# alarm_module.net
KiCad netlist of a schematic drawn in Altium Designer
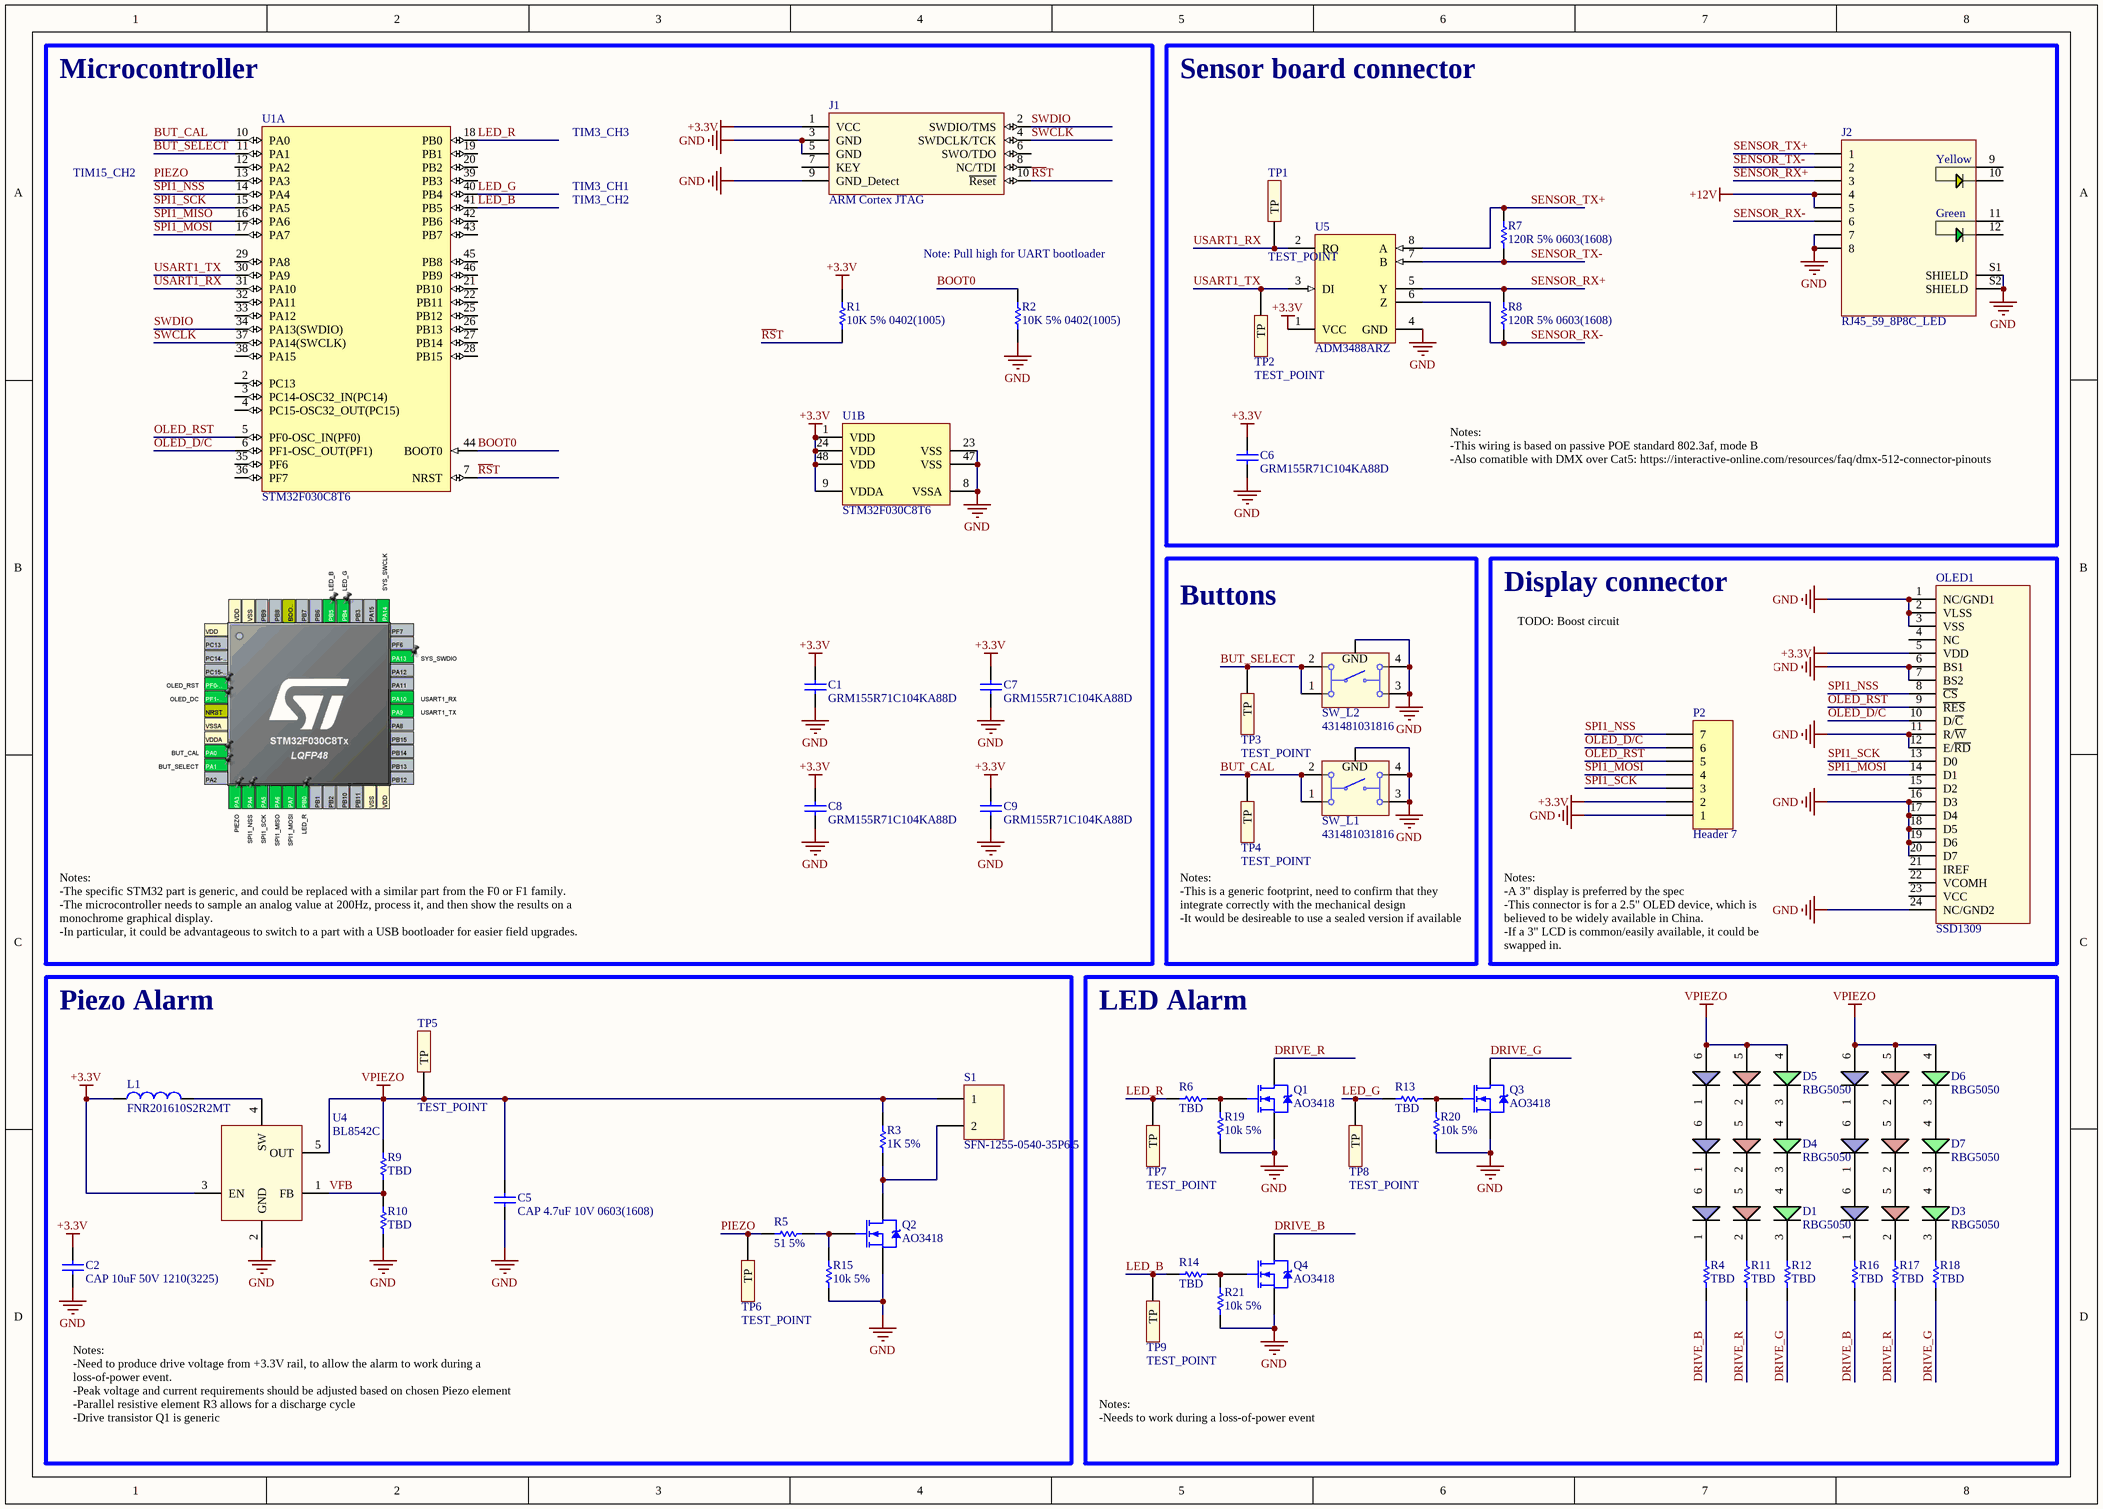
[diagram p0: alarm_module.SchDoc]

(export (version "E")
  (design (tool "Eeschema 10.0.6"))
  (components
    (comp (ref "C1")
      (value "GRM155R71C104KA88D")
      (footprint "CAPC1005X55X25ML05T10")
      (description "Chip Capacitor, 0.1 uF, +/- 10%, 16 V, -55 to 125 degC, 0402 (1005 Metric), RoHS, Tape and Reel")
      (fields (field (name "VOLTAGE") "16V") (field (name "TOLERANCE") "10%"))
      (libsource (lib "Altium Content Vault") (part "CAP-NP-2"))
    )
    (comp (ref "C2")
      (value "CAP 10uF 50V 1210(3225)")
      (footprint "CAPC1210(3225)190_N")
      (description "CAP 10uF 50V -20% to +80% 1210 (3225 Metric) Thickness 1.9mm SMD")
      (fields (field (name "TOLERANCE") "-20% to +80%"))
      (libsource (lib "Altium Content Vault") (part "CAP"))
    )
    (comp (ref "C5")
      (value "CAP 4.7uF 10V 0603(1608)")
      (footprint "CAPC0603(1608)55_L")
      (description "CAP 4.7uF 10V ±10% 0603 (1608 Metric) Thickness 0.55mm SMD")
      (fields (field (name "TOLERANCE") "Â±10%"))
      (libsource (lib "Altium Content Vault") (part "CAP"))
    )
    (comp (ref "C6")
      (value "GRM155R71C104KA88D")
      (footprint "CAPC1005X55X25ML05T10")
      (description "Chip Capacitor, 0.1 uF, +/- 10%, 16 V, -55 to 125 degC, 0402 (1005 Metric), RoHS, Tape and Reel")
      (fields (field (name "VOLTAGE") "16V") (field (name "TOLERANCE") "10%"))
      (libsource (lib "Altium Content Vault") (part "CAP-NP-2"))
    )
    (comp (ref "C7")
      (value "GRM155R71C104KA88D")
      (footprint "CAPC1005X55X25ML05T10")
      (description "Chip Capacitor, 0.1 uF, +/- 10%, 16 V, -55 to 125 degC, 0402 (1005 Metric), RoHS, Tape and Reel")
      (fields (field (name "VOLTAGE") "16V") (field (name "TOLERANCE") "10%"))
      (libsource (lib "Altium Content Vault") (part "CAP-NP-2"))
    )
    (comp (ref "C8")
      (value "GRM155R71C104KA88D")
      (footprint "CAPC1005X55X25ML05T10")
      (description "Chip Capacitor, 0.1 uF, +/- 10%, 16 V, -55 to 125 degC, 0402 (1005 Metric), RoHS, Tape and Reel")
      (fields (field (name "VOLTAGE") "16V") (field (name "TOLERANCE") "10%"))
      (libsource (lib "Altium Content Vault") (part "CAP-NP-2"))
    )
    (comp (ref "C9")
      (value "GRM155R71C104KA88D")
      (footprint "CAPC1005X55X25ML05T10")
      (description "Chip Capacitor, 0.1 uF, +/- 10%, 16 V, -55 to 125 degC, 0402 (1005 Metric), RoHS, Tape and Reel")
      (fields (field (name "VOLTAGE") "16V") (field (name "TOLERANCE") "10%"))
      (libsource (lib "Altium Content Vault") (part "CAP-NP-2"))
    )
    (comp (ref "D1")
      (value "RBG5050")
      (footprint "5050RGB")
      (description "Generic RGB LED in 5050 package. Note that several variants exist, so check the pinout!")
      (fields (field (name "PARTNUMBER") "Unknown/Generic"))
      (libsource (lib "Blinkinlabs") (part "RBG5050"))
    )
    (comp (ref "D3")
      (value "RBG5050")
      (footprint "5050RGB")
      (description "Generic RGB LED in 5050 package. Note that several variants exist, so check the pinout!")
      (fields (field (name "PARTNUMBER") "Unknown/Generic"))
      (libsource (lib "Blinkinlabs") (part "RBG5050"))
    )
    (comp (ref "D4")
      (value "RBG5050")
      (footprint "5050RGB")
      (description "Generic RGB LED in 5050 package. Note that several variants exist, so check the pinout!")
      (fields (field (name "PARTNUMBER") "Unknown/Generic"))
      (libsource (lib "Blinkinlabs") (part "RBG5050"))
    )
    (comp (ref "D5")
      (value "RBG5050")
      (footprint "5050RGB")
      (description "Generic RGB LED in 5050 package. Note that several variants exist, so check the pinout!")
      (fields (field (name "PARTNUMBER") "Unknown/Generic"))
      (libsource (lib "Blinkinlabs") (part "RBG5050"))
    )
    (comp (ref "D6")
      (value "RBG5050")
      (footprint "5050RGB")
      (description "Generic RGB LED in 5050 package. Note that several variants exist, so check the pinout!")
      (fields (field (name "PARTNUMBER") "Unknown/Generic"))
      (libsource (lib "Blinkinlabs") (part "RBG5050"))
    )
    (comp (ref "D7")
      (value "RBG5050")
      (footprint "5050RGB")
      (description "Generic RGB LED in 5050 package. Note that several variants exist, so check the pinout!")
      (fields (field (name "PARTNUMBER") "Unknown/Generic"))
      (libsource (lib "Blinkinlabs") (part "RBG5050"))
    )
    (comp (ref "J1")
      (value "ARM Cortex JTAG")
      (footprint "1.27mm 2x5 SMD Header")
      (description "Arm Cortex 10-pin JTAG connector")
      (fields (field (name "MANUFACTURER") "Unknown/Generic") (field (name "PARTNUMBER") "unknown/Generic"))
      (libsource (lib "Blinkinlabs") (part "ARM Cortex JTAG"))
    )
    (comp (ref "J2")
      (value "RJ45_59_8P8C_LED")
      (footprint "RJ45_59_8P8C_LED")
      (description "Generic RJ49 jack with LED and without magnetics")
      (fields (field (name "MANUFACTURER") "Unknown/Generic"))
      (libsource (lib "Blinkinlabs") (part "RJ45_59_8P8C_LED"))
    )
    (comp (ref "L1")
      (value "FNR201610S2R2MT")
      (footprint "FNR201610S")
      (description "Wire Wound SMD Power Inductors 2.0×1.6×1.0 2.2uH")
      (libsource (lib "Blinkinlabs") (part "FNR201610S2R2MT"))
    )
    (comp (ref "OLED1")
      (value "SSD1309")
      (description "2.4\" OLED display, 24-pin connector, SSD1309 driver IC")
      (libsource (lib "Blinkinlabs") (part "SSD1309"))
    )
    (comp (ref "P2")
      (value "Header 7")
      (footprint "HDR1X7")
      (description "Header, 7-Pin")
      (fields (field (name "PUBLISHER") "Altium Limited"))
      (libsource (lib "Miscellaneous Connectors") (part "Header 7"))
    )
    (comp (ref "Q1")
      (value "AO3418")
      (footprint "SOT95P280X125-3N")
      (description "30V N-Channel MOSFET")
      (fields (field (name "MANUFACTURER") "Alpha & Omega"))
      (libsource (lib "Blinkinlabs") (part "AO3418"))
    )
    (comp (ref "Q2")
      (value "AO3418")
      (footprint "SOT95P280X125-3N")
      (description "30V N-Channel MOSFET")
      (fields (field (name "MANUFACTURER") "Alpha & Omega"))
      (libsource (lib "Blinkinlabs") (part "AO3418"))
    )
    (comp (ref "Q3")
      (value "AO3418")
      (footprint "SOT95P280X125-3N")
      (description "30V N-Channel MOSFET")
      (fields (field (name "MANUFACTURER") "Alpha & Omega"))
      (libsource (lib "Blinkinlabs") (part "AO3418"))
    )
    (comp (ref "Q4")
      (value "AO3418")
      (footprint "SOT95P280X125-3N")
      (description "30V N-Channel MOSFET")
      (fields (field (name "MANUFACTURER") "Alpha & Omega"))
      (libsource (lib "Blinkinlabs") (part "AO3418"))
    )
    (comp (ref "R1")
      (value "10K 5% 0402(1005)")
      (footprint "RESC0402(1005)_N")
      (description "10K 0.063W 5% 0402 (1005 Metric)  SMD")
      (fields (field (name "TOLERANCE") "5 %") (field (name "POWER") "0.063 W"))
      (libsource (lib "Altium Content Vault") (part "RES"))
    )
    (comp (ref "R2")
      (value "10K 5% 0402(1005)")
      (footprint "RESC0402(1005)_N")
      (description "10K 0.063W 5% 0402 (1005 Metric)  SMD")
      (fields (field (name "TOLERANCE") "5 %") (field (name "POWER") "0.063 W"))
      (libsource (lib "Altium Content Vault") (part "RES"))
    )
    (comp (ref "R3")
      (value "1K 5%")
      (footprint "RESC0402(1005)_N")
      (description "10K 0.063W 5% 0402 (1005 Metric)  SMD")
      (fields (field (name "TOLERANCE") "5 %") (field (name "POWER") "0.063 W"))
      (libsource (lib "Altium Content Vault") (part "RES"))
    )
    (comp (ref "R4")
      (value "TBD")
      (footprint "RESC0402(1005)_N")
      (description "10K 0.063W 5% 0402 (1005 Metric)  SMD")
      (fields (field (name "TOLERANCE") "5 %") (field (name "POWER") "0.063 W"))
      (libsource (lib "Altium Content Vault") (part "RES"))
    )
    (comp (ref "R5")
      (value "51 5%")
      (footprint "RESC0402(1005)_N")
      (description "10K 0.063W 5% 0402 (1005 Metric)  SMD")
      (fields (field (name "TOLERANCE") "5 %") (field (name "POWER") "0.063 W"))
      (libsource (lib "Altium Content Vault") (part "RES"))
    )
    (comp (ref "R6")
      (value "TBD")
      (footprint "RESC0402(1005)_N")
      (description "10K 0.063W 5% 0402 (1005 Metric)  SMD")
      (fields (field (name "TOLERANCE") "5 %") (field (name "POWER") "0.063 W"))
      (libsource (lib "Altium Content Vault") (part "RES"))
    )
    (comp (ref "R7")
      (value "120R 5% 0603(1608)")
      (footprint "RESC0603(1608)_L")
      (description "120R 0.1W 5% 0603 (1608 Metric)  SMD")
      (fields (field (name "POWER") "0.1 W") (field (name "TOLERANCE") "5 %"))
      (libsource (lib "Altium Content Vault") (part "RES"))
    )
    (comp (ref "R8")
      (value "120R 5% 0603(1608)")
      (footprint "RESC0603(1608)_L")
      (description "120R 0.1W 5% 0603 (1608 Metric)  SMD")
      (fields (field (name "POWER") "0.1 W") (field (name "TOLERANCE") "5 %"))
      (libsource (lib "Altium Content Vault") (part "RES"))
    )
    (comp (ref "R9")
      (value "TBD")
      (footprint "RESC0402(1005)_N")
      (description "10K 0.063W 5% 0402 (1005 Metric)  SMD")
      (fields (field (name "TOLERANCE") "5 %") (field (name "POWER") "0.063 W"))
      (libsource (lib "Altium Content Vault") (part "RES"))
    )
    (comp (ref "R10")
      (value "TBD")
      (footprint "RESC0402(1005)_N")
      (description "10K 0.063W 5% 0402 (1005 Metric)  SMD")
      (fields (field (name "TOLERANCE") "5 %") (field (name "POWER") "0.063 W"))
      (libsource (lib "Altium Content Vault") (part "RES"))
    )
    (comp (ref "R11")
      (value "TBD")
      (footprint "RESC0402(1005)_N")
      (description "10K 0.063W 5% 0402 (1005 Metric)  SMD")
      (fields (field (name "TOLERANCE") "5 %") (field (name "POWER") "0.063 W"))
      (libsource (lib "Altium Content Vault") (part "RES"))
    )
    (comp (ref "R12")
      (value "TBD")
      (footprint "RESC0402(1005)_N")
      (description "10K 0.063W 5% 0402 (1005 Metric)  SMD")
      (fields (field (name "TOLERANCE") "5 %") (field (name "POWER") "0.063 W"))
      (libsource (lib "Altium Content Vault") (part "RES"))
    )
    (comp (ref "R13")
      (value "TBD")
      (footprint "RESC0402(1005)_N")
      (description "10K 0.063W 5% 0402 (1005 Metric)  SMD")
      (fields (field (name "TOLERANCE") "5 %") (field (name "POWER") "0.063 W"))
      (libsource (lib "Altium Content Vault") (part "RES"))
    )
    (comp (ref "R14")
      (value "TBD")
      (footprint "RESC0402(1005)_N")
      (description "10K 0.063W 5% 0402 (1005 Metric)  SMD")
      (fields (field (name "TOLERANCE") "5 %") (field (name "POWER") "0.063 W"))
      (libsource (lib "Altium Content Vault") (part "RES"))
    )
    (comp (ref "R15")
      (value "10k 5%")
      (footprint "RESC0402(1005)_N")
      (description "10K 0.063W 5% 0402 (1005 Metric)  SMD")
      (fields (field (name "TOLERANCE") "5 %") (field (name "POWER") "0.063 W"))
      (libsource (lib "Altium Content Vault") (part "RES"))
    )
    (comp (ref "R16")
      (value "TBD")
      (footprint "RESC0402(1005)_N")
      (description "10K 0.063W 5% 0402 (1005 Metric)  SMD")
      (fields (field (name "TOLERANCE") "5 %") (field (name "POWER") "0.063 W"))
      (libsource (lib "Altium Content Vault") (part "RES"))
    )
    (comp (ref "R17")
      (value "TBD")
      (footprint "RESC0402(1005)_N")
      (description "10K 0.063W 5% 0402 (1005 Metric)  SMD")
      (fields (field (name "TOLERANCE") "5 %") (field (name "POWER") "0.063 W"))
      (libsource (lib "Altium Content Vault") (part "RES"))
    )
    (comp (ref "R18")
      (value "TBD")
      (footprint "RESC0402(1005)_N")
      (description "10K 0.063W 5% 0402 (1005 Metric)  SMD")
      (fields (field (name "TOLERANCE") "5 %") (field (name "POWER") "0.063 W"))
      (libsource (lib "Altium Content Vault") (part "RES"))
    )
    (comp (ref "R19")
      (value "10k 5%")
      (footprint "RESC0402(1005)_N")
      (description "10K 0.063W 5% 0402 (1005 Metric)  SMD")
      (fields (field (name "TOLERANCE") "5 %") (field (name "POWER") "0.063 W"))
      (libsource (lib "Altium Content Vault") (part "RES"))
    )
    (comp (ref "R20")
      (value "10k 5%")
      (footprint "RESC0402(1005)_N")
      (description "10K 0.063W 5% 0402 (1005 Metric)  SMD")
      (fields (field (name "TOLERANCE") "5 %") (field (name "POWER") "0.063 W"))
      (libsource (lib "Altium Content Vault") (part "RES"))
    )
    (comp (ref "R21")
      (value "10k 5%")
      (footprint "RESC0402(1005)_N")
      (description "10K 0.063W 5% 0402 (1005 Metric)  SMD")
      (fields (field (name "TOLERANCE") "5 %") (field (name "POWER") "0.063 W"))
      (libsource (lib "Altium Content Vault") (part "RES"))
    )
    (comp (ref "S1")
      (value "SFN-1255-0540-35P6.5")
      (footprint "SFN-1255-0540-35P6.5")
      (description "Piezo Buzzer, 4KHz")
      (fields (field (name "MANUFACTURER") "S&S"))
      (libsource (lib "Blinkinlabs") (part "SFN-1255-0540-35P6.5"))
    )
    (comp (ref "SW_L1")
      (value "431481031816")
      (footprint "431481031816")
      (description "WS-TASV SMD Tact Switch 6X6 mm with ground terminal")
      (fields (field (name "MANUFACTURER") "Wuerth Elektronik"))
      (libsource (lib "Altium Content Vault") (part "WE-TACT-SW-5"))
    )
    (comp (ref "SW_L2")
      (value "431481031816")
      (footprint "431481031816")
      (description "WS-TASV SMD Tact Switch 6X6 mm with ground terminal")
      (fields (field (name "MANUFACTURER") "Wuerth Elektronik"))
      (libsource (lib "Altium Content Vault") (part "WE-TACT-SW-5"))
    )
    (comp (ref "TP1")
      (value "TEST_POINT")
      (footprint "TP-SMD-1mm")
      (description "Test point")
      (libsource (lib "Blinkinlabs") (part "TEST_POINT"))
    )
    (comp (ref "TP2")
      (value "TEST_POINT")
      (footprint "TP-SMD-1mm")
      (description "Test point")
      (libsource (lib "") (part "TEST_POINT_1"))
    )
    (comp (ref "TP3")
      (value "TEST_POINT")
      (footprint "TP-SMD-1mm")
      (description "Test point")
      (libsource (lib "") (part "TEST_POINT_1"))
    )
    (comp (ref "TP4")
      (value "TEST_POINT")
      (footprint "TP-SMD-1mm")
      (description "Test point")
      (libsource (lib "") (part "TEST_POINT_1"))
    )
    (comp (ref "TP5")
      (value "TEST_POINT")
      (footprint "TP-SMD-1mm")
      (description "Test point")
      (libsource (lib "Blinkinlabs") (part "TEST_POINT"))
    )
    (comp (ref "TP6")
      (value "TEST_POINT")
      (footprint "TP-SMD-1mm")
      (description "Test point")
      (libsource (lib "") (part "TEST_POINT_1"))
    )
    (comp (ref "TP7")
      (value "TEST_POINT")
      (footprint "TP-SMD-1mm")
      (description "Test point")
      (libsource (lib "") (part "TEST_POINT_1"))
    )
    (comp (ref "TP8")
      (value "TEST_POINT")
      (footprint "TP-SMD-1mm")
      (description "Test point")
      (libsource (lib "") (part "TEST_POINT_1"))
    )
    (comp (ref "TP9")
      (value "TEST_POINT")
      (footprint "TP-SMD-1mm")
      (description "Test point")
      (libsource (lib "") (part "TEST_POINT_1"))
    )
    (comp (ref "U1")
      (value "STM32F030C8T6")
      (footprint "STM-LQFP48_M")
      (libsource (lib "Altium Content Vault") (part "MC-ARM-STM32F030_X8-SQ48"))
    )
    (comp (ref "U4")
      (value "BL8542C")
      (footprint "SOT95P280X130-5N")
      (description "0.85V startup, 1MHz, 300mA Iout,  Synchronous Boost Converter (adjustable output)")
      (fields (field (name "MANUFACTURER") "Belling"))
      (libsource (lib "Blinkinlabs") (part "BL8542C"))
    )
    (comp (ref "U5")
      (value "ADM3488ARZ")
      (footprint "ADI-R-8_L")
      (fields (field (name "MANUFACTURER") "Analog Devices"))
      (libsource (lib "Altium Content Vault") (part "ADI-ADM3488_90-R-8"))
    )
  )
  (nets
    (net (code "1") (name "+3.3V") (class "Default")
      (node (ref "C1") (pin "2") (pinfunction "2_2") (pintype "passive"))
      (node (ref "C2") (pin "2") (pinfunction "2_2") (pintype "passive"))
      (node (ref "C6") (pin "2") (pinfunction "2_2") (pintype "passive"))
      (node (ref "C7") (pin "2") (pinfunction "2_2") (pintype "passive"))
      (node (ref "C8") (pin "2") (pinfunction "2_2") (pintype "passive"))
      (node (ref "C9") (pin "2") (pinfunction "2_2") (pintype "passive"))
      (node (ref "J1") (pin "1") (pinfunction "VCC_1") (pintype "power_in"))
      (node (ref "L1") (pin "1") (pinfunction "1_1") (pintype "passive"))
      (node (ref "OLED1") (pin "5") (pinfunction "VDD_5") (pintype "passive"))
      (node (ref "P2") (pin "2") (pinfunction "2_2") (pintype "passive"))
      (node (ref "R1") (pin "1") (pinfunction "1_1") (pintype "passive"))
      (node (ref "U1") (pin "1") (pinfunction "VDD_1") (pintype "power_in"))
      (node (ref "U1") (pin "24") (pinfunction "VDD_24") (pintype "power_in"))
      (node (ref "U1") (pin "48") (pinfunction "VDD_48") (pintype "power_in"))
      (node (ref "U1") (pin "9") (pinfunction "VDDA_9") (pintype "power_in"))
      (node (ref "U4") (pin "3") (pinfunction "EN_3") (pintype "passive"))
      (node (ref "U5") (pin "1") (pinfunction "VCC_1") (pintype "power_in"))
    )
    (net (code "2") (name "+12V") (class "Default")
      (node (ref "J2") (pin "4") (pinfunction "4_4") (pintype "passive"))
      (node (ref "J2") (pin "5") (pinfunction "5_5") (pintype "passive"))
    )
    (net (code "3") (name "/BOOT0") (class "Default")
      (node (ref "R2") (pin "1") (pinfunction "1_1") (pintype "passive"))
      (node (ref "U1") (pin "44") (pinfunction "BOOT0_44") (pintype "input"))
    )
    (net (code "4") (name "/BUT_CAL") (class "Default")
      (node (ref "SW_L1") (pin "1") (pinfunction "1_1") (pintype "passive"))
      (node (ref "SW_L1") (pin "2") (pinfunction "2_2") (pintype "passive"))
      (node (ref "TP4") (pin "1") (pinfunction "TP_1") (pintype "passive"))
      (node (ref "U1") (pin "10") (pinfunction "PA0_10") (pintype "bidirectional"))
    )
    (net (code "5") (name "/BUT_SELECT") (class "Default")
      (node (ref "SW_L2") (pin "1") (pinfunction "1_1") (pintype "passive"))
      (node (ref "SW_L2") (pin "2") (pinfunction "2_2") (pintype "passive"))
      (node (ref "TP3") (pin "1") (pinfunction "TP_1") (pintype "passive"))
      (node (ref "U1") (pin "11") (pinfunction "PA1_11") (pintype "bidirectional"))
    )
    (net (code "6") (name "/DRIVE_B") (class "Default")
      (node (ref "Q4") (pin "3") (pinfunction "DRAIN_3") (pintype "passive"))
      (node (ref "R16") (pin "1") (pinfunction "1_1") (pintype "passive"))
      (node (ref "R4") (pin "1") (pinfunction "1_1") (pintype "passive"))
    )
    (net (code "7") (name "/DRIVE_G") (class "Default")
      (node (ref "Q3") (pin "3") (pinfunction "DRAIN_3") (pintype "passive"))
      (node (ref "R12") (pin "1") (pinfunction "1_1") (pintype "passive"))
      (node (ref "R18") (pin "1") (pinfunction "1_1") (pintype "passive"))
    )
    (net (code "8") (name "/DRIVE_R") (class "Default")
      (node (ref "Q1") (pin "3") (pinfunction "DRAIN_3") (pintype "passive"))
      (node (ref "R11") (pin "1") (pinfunction "1_1") (pintype "passive"))
      (node (ref "R17") (pin "1") (pinfunction "1_1") (pintype "passive"))
    )
    (net (code "9") (name "/LED_B") (class "Default")
      (node (ref "R14") (pin "1") (pinfunction "1_1") (pintype "passive"))
      (node (ref "TP9") (pin "1") (pinfunction "TP_1") (pintype "passive"))
      (node (ref "U1") (pin "41") (pinfunction "PB5_41") (pintype "bidirectional"))
    )
    (net (code "10") (name "/LED_G") (class "Default")
      (node (ref "R13") (pin "1") (pinfunction "1_1") (pintype "passive"))
      (node (ref "TP8") (pin "1") (pinfunction "TP_1") (pintype "passive"))
      (node (ref "U1") (pin "40") (pinfunction "PB4_40") (pintype "bidirectional"))
    )
    (net (code "11") (name "/LED_R") (class "Default")
      (node (ref "R6") (pin "1") (pinfunction "1_1") (pintype "passive"))
      (node (ref "TP7") (pin "1") (pinfunction "TP_1") (pintype "passive"))
      (node (ref "U1") (pin "18") (pinfunction "PB0_18") (pintype "bidirectional"))
    )
    (net (code "12") (name "/OLED_D{slash}C") (class "Default")
      (node (ref "OLED1") (pin "10") (pinfunction "D/~{C}_10") (pintype "passive"))
      (node (ref "P2") (pin "6") (pinfunction "6_6") (pintype "passive"))
      (node (ref "U1") (pin "6") (pinfunction "PF1-OSC_OUT(PF1)_6") (pintype "bidirectional"))
    )
    (net (code "13") (name "/OLED_RST") (class "Default")
      (node (ref "OLED1") (pin "9") (pinfunction "~{RES}_9") (pintype "passive"))
      (node (ref "P2") (pin "5") (pinfunction "5_5") (pintype "passive"))
      (node (ref "U1") (pin "5") (pinfunction "PF0-OSC_IN(PF0)_5") (pintype "bidirectional"))
    )
    (net (code "14") (name "/PIEZO") (class "Default")
      (node (ref "R5") (pin "1") (pinfunction "1_1") (pintype "passive"))
      (node (ref "TP6") (pin "1") (pinfunction "TP_1") (pintype "passive"))
      (node (ref "U1") (pin "13") (pinfunction "PA3_13") (pintype "bidirectional"))
    )
    (net (code "15") (name "/SENSOR_RX+") (class "Default")
      (node (ref "J2") (pin "3") (pinfunction "3_3") (pintype "passive"))
      (node (ref "R8") (pin "2") (pinfunction "2_2") (pintype "passive"))
      (node (ref "U5") (pin "5") (pinfunction "Y_5") (pintype "tri_state"))
    )
    (net (code "16") (name "/SENSOR_RX-") (class "Default")
      (node (ref "J2") (pin "6") (pinfunction "6_6") (pintype "passive"))
      (node (ref "R8") (pin "1") (pinfunction "1_1") (pintype "passive"))
      (node (ref "U5") (pin "6") (pinfunction "Z_6") (pintype "tri_state"))
    )
    (net (code "17") (name "/SENSOR_TX+") (class "Default")
      (node (ref "J2") (pin "1") (pinfunction "1_1") (pintype "passive"))
      (node (ref "R7") (pin "2") (pinfunction "2_2") (pintype "passive"))
      (node (ref "U5") (pin "8") (pinfunction "A_8") (pintype "input"))
    )
    (net (code "18") (name "/SENSOR_TX-") (class "Default")
      (node (ref "J2") (pin "2") (pinfunction "2_2") (pintype "passive"))
      (node (ref "R7") (pin "1") (pinfunction "1_1") (pintype "passive"))
      (node (ref "U5") (pin "7") (pinfunction "B_7") (pintype "input"))
    )
    (net (code "19") (name "/SPI1_MISO") (class "Default")
      (node (ref "U1") (pin "16") (pinfunction "PA6_16") (pintype "bidirectional"))
    )
    (net (code "20") (name "/SPI1_MOSI") (class "Default")
      (node (ref "OLED1") (pin "14") (pinfunction "D1_14") (pintype "passive"))
      (node (ref "P2") (pin "4") (pinfunction "4_4") (pintype "passive"))
      (node (ref "U1") (pin "17") (pinfunction "PA7_17") (pintype "bidirectional"))
    )
    (net (code "21") (name "/SPI1_NSS") (class "Default")
      (node (ref "OLED1") (pin "8") (pinfunction "~{CS}_8") (pintype "passive"))
      (node (ref "P2") (pin "7") (pinfunction "7_7") (pintype "passive"))
      (node (ref "U1") (pin "14") (pinfunction "PA4_14") (pintype "bidirectional"))
    )
    (net (code "22") (name "/SPI1_SCK") (class "Default")
      (node (ref "OLED1") (pin "13") (pinfunction "D0_13") (pintype "passive"))
      (node (ref "P2") (pin "3") (pinfunction "3_3") (pintype "passive"))
      (node (ref "U1") (pin "15") (pinfunction "PA5_15") (pintype "bidirectional"))
    )
    (net (code "23") (name "/SWCLK") (class "Default")
      (node (ref "J1") (pin "4") (pinfunction "SWDCLK/TCK_4") (pintype "bidirectional"))
      (node (ref "U1") (pin "37") (pinfunction "PA14(SWCLK)_37") (pintype "bidirectional"))
    )
    (net (code "24") (name "/SWDIO") (class "Default")
      (node (ref "J1") (pin "2") (pinfunction "SWDIO/TMS_2") (pintype "bidirectional"))
      (node (ref "U1") (pin "34") (pinfunction "PA13(SWDIO)_34") (pintype "bidirectional"))
    )
    (net (code "25") (name "/USART1_RX") (class "Default")
      (node (ref "TP1") (pin "1") (pinfunction "TP_1") (pintype "passive"))
      (node (ref "U1") (pin "31") (pinfunction "PA10_31") (pintype "bidirectional"))
      (node (ref "U5") (pin "2") (pinfunction "RO_2") (pintype "tri_state"))
    )
    (net (code "26") (name "/USART1_TX") (class "Default")
      (node (ref "TP2") (pin "1") (pinfunction "TP_1") (pintype "passive"))
      (node (ref "U1") (pin "30") (pinfunction "PA9_30") (pintype "bidirectional"))
      (node (ref "U5") (pin "3") (pinfunction "DI_3") (pintype "input"))
    )
    (net (code "27") (name "/VFB") (class "Default")
      (node (ref "R10") (pin "2") (pinfunction "2_2") (pintype "passive"))
      (node (ref "R9") (pin "1") (pinfunction "1_1") (pintype "passive"))
      (node (ref "U4") (pin "1") (pinfunction "FB_1") (pintype "passive"))
    )
    (net (code "28") (name "/~{RS}T") (class "Default")
      (node (ref "J1") (pin "10") (pinfunction "~{Reset}_10") (pintype "bidirectional"))
      (node (ref "R1") (pin "2") (pinfunction "2_2") (pintype "passive"))
      (node (ref "U1") (pin "7") (pinfunction "NRST_7") (pintype "bidirectional"))
    )
    (net (code "29") (name "GND") (class "Default")
      (node (ref "C1") (pin "1") (pinfunction "1_1") (pintype "passive"))
      (node (ref "C2") (pin "1") (pinfunction "1_1") (pintype "passive"))
      (node (ref "C5") (pin "1") (pinfunction "1_1") (pintype "passive"))
      (node (ref "C6") (pin "1") (pinfunction "1_1") (pintype "passive"))
      (node (ref "C7") (pin "1") (pinfunction "1_1") (pintype "passive"))
      (node (ref "C8") (pin "1") (pinfunction "1_1") (pintype "passive"))
      (node (ref "C9") (pin "1") (pinfunction "1_1") (pintype "passive"))
      (node (ref "J1") (pin "3") (pinfunction "GND_3") (pintype "power_in"))
      (node (ref "J1") (pin "5") (pinfunction "GND_5") (pintype "power_in"))
      (node (ref "J1") (pin "9") (pinfunction "GND_Detect_9") (pintype "power_in"))
      (node (ref "J2") (pin "7") (pinfunction "7_7") (pintype "passive"))
      (node (ref "J2") (pin "8") (pinfunction "8_8") (pintype "passive"))
      (node (ref "J2") (pin "S1") (pinfunction "SHIELD_S1") (pintype "passive"))
      (node (ref "J2") (pin "S2") (pinfunction "SHIELD_S2") (pintype "passive"))
      (node (ref "OLED1") (pin "1") (pinfunction "NC/GND1_1") (pintype "power_in"))
      (node (ref "OLED1") (pin "11") (pinfunction "R/~{W}_11") (pintype "passive"))
      (node (ref "OLED1") (pin "12") (pinfunction "E/~{RD}_12") (pintype "passive"))
      (node (ref "OLED1") (pin "16") (pinfunction "D3_16") (pintype "passive"))
      (node (ref "OLED1") (pin "17") (pinfunction "D4_17") (pintype "passive"))
      (node (ref "OLED1") (pin "18") (pinfunction "D5_18") (pintype "passive"))
      (node (ref "OLED1") (pin "19") (pinfunction "D6_19") (pintype "passive"))
      (node (ref "OLED1") (pin "2") (pinfunction "VLSS_2") (pintype "passive"))
      (node (ref "OLED1") (pin "20") (pinfunction "D7_20") (pintype "passive"))
      (node (ref "OLED1") (pin "24") (pinfunction "NC/GND2_24") (pintype "passive"))
      (node (ref "OLED1") (pin "3") (pinfunction "VSS_3") (pintype "passive"))
      (node (ref "OLED1") (pin "6") (pinfunction "BS1_6") (pintype "passive"))
      (node (ref "OLED1") (pin "7") (pinfunction "BS2_7") (pintype "passive"))
      (node (ref "P2") (pin "1") (pinfunction "1_1") (pintype "passive"))
      (node (ref "Q1") (pin "2") (pinfunction "SOURCE_2") (pintype "passive"))
      (node (ref "Q2") (pin "2") (pinfunction "SOURCE_2") (pintype "passive"))
      (node (ref "Q3") (pin "2") (pinfunction "SOURCE_2") (pintype "passive"))
      (node (ref "Q4") (pin "2") (pinfunction "SOURCE_2") (pintype "passive"))
      (node (ref "R10") (pin "1") (pinfunction "1_1") (pintype "passive"))
      (node (ref "R15") (pin "1") (pinfunction "1_1") (pintype "passive"))
      (node (ref "R19") (pin "1") (pinfunction "1_1") (pintype "passive"))
      (node (ref "R2") (pin "2") (pinfunction "2_2") (pintype "passive"))
      (node (ref "R20") (pin "1") (pinfunction "1_1") (pintype "passive"))
      (node (ref "R21") (pin "1") (pinfunction "1_1") (pintype "passive"))
      (node (ref "SW_L1") (pin "3") (pinfunction "3_3") (pintype "passive"))
      (node (ref "SW_L1") (pin "4") (pinfunction "4_4") (pintype "passive"))
      (node (ref "SW_L1") (pin "5") (pinfunction "5_5") (pintype "passive"))
      (node (ref "SW_L2") (pin "3") (pinfunction "3_3") (pintype "passive"))
      (node (ref "SW_L2") (pin "4") (pinfunction "4_4") (pintype "passive"))
      (node (ref "SW_L2") (pin "5") (pinfunction "5_5") (pintype "passive"))
      (node (ref "U1") (pin "23") (pinfunction "VSS_23") (pintype "power_in"))
      (node (ref "U1") (pin "47") (pinfunction "VSS_47") (pintype "power_in"))
      (node (ref "U1") (pin "8") (pinfunction "VSSA_8") (pintype "power_in"))
      (node (ref "U4") (pin "2") (pinfunction "GND_2") (pintype "passive"))
      (node (ref "U5") (pin "4") (pinfunction "GND_4") (pintype "power_in"))
    )
    (net (code "30") (name "Net-(D1-Pad1)") (class "Default")
      (node (ref "D1") (pin "1") (pinfunction "1_1") (pintype "passive"))
      (node (ref "R4") (pin "2") (pinfunction "2_2") (pintype "passive"))
    )
    (net (code "31") (name "Net-(D1-Pad2)") (class "Default")
      (node (ref "D1") (pin "2") (pinfunction "2_2") (pintype "passive"))
      (node (ref "R11") (pin "2") (pinfunction "2_2") (pintype "passive"))
    )
    (net (code "32") (name "Net-(D1-Pad3)") (class "Default")
      (node (ref "D1") (pin "3") (pinfunction "3_3") (pintype "passive"))
      (node (ref "R12") (pin "2") (pinfunction "2_2") (pintype "passive"))
    )
    (net (code "33") (name "Net-(D1-Pad4)") (class "Default")
      (node (ref "D1") (pin "4") (pinfunction "4_4") (pintype "passive"))
      (node (ref "D4") (pin "3") (pinfunction "3_3") (pintype "passive"))
    )
    (net (code "34") (name "Net-(D1-Pad5)") (class "Default")
      (node (ref "D1") (pin "5") (pinfunction "5_5") (pintype "passive"))
      (node (ref "D4") (pin "2") (pinfunction "2_2") (pintype "passive"))
    )
    (net (code "35") (name "Net-(D1-Pad6)") (class "Default")
      (node (ref "D1") (pin "6") (pinfunction "6_6") (pintype "passive"))
      (node (ref "D4") (pin "1") (pinfunction "1_1") (pintype "passive"))
    )
    (net (code "36") (name "Net-(D3-Pad1)") (class "Default")
      (node (ref "D3") (pin "1") (pinfunction "1_1") (pintype "passive"))
      (node (ref "R16") (pin "2") (pinfunction "2_2") (pintype "passive"))
    )
    (net (code "37") (name "Net-(D3-Pad2)") (class "Default")
      (node (ref "D3") (pin "2") (pinfunction "2_2") (pintype "passive"))
      (node (ref "R17") (pin "2") (pinfunction "2_2") (pintype "passive"))
    )
    (net (code "38") (name "Net-(D3-Pad3)") (class "Default")
      (node (ref "D3") (pin "3") (pinfunction "3_3") (pintype "passive"))
      (node (ref "R18") (pin "2") (pinfunction "2_2") (pintype "passive"))
    )
    (net (code "39") (name "Net-(D3-Pad4)") (class "Default")
      (node (ref "D3") (pin "4") (pinfunction "4_4") (pintype "passive"))
      (node (ref "D7") (pin "3") (pinfunction "3_3") (pintype "passive"))
    )
    (net (code "40") (name "Net-(D3-Pad5)") (class "Default")
      (node (ref "D3") (pin "5") (pinfunction "5_5") (pintype "passive"))
      (node (ref "D7") (pin "2") (pinfunction "2_2") (pintype "passive"))
    )
    (net (code "41") (name "Net-(D3-Pad6)") (class "Default")
      (node (ref "D3") (pin "6") (pinfunction "6_6") (pintype "passive"))
      (node (ref "D7") (pin "1") (pinfunction "1_1") (pintype "passive"))
    )
    (net (code "42") (name "Net-(D4-Pad4)") (class "Default")
      (node (ref "D4") (pin "4") (pinfunction "4_4") (pintype "passive"))
      (node (ref "D5") (pin "3") (pinfunction "3_3") (pintype "passive"))
    )
    (net (code "43") (name "Net-(D4-Pad5)") (class "Default")
      (node (ref "D4") (pin "5") (pinfunction "5_5") (pintype "passive"))
      (node (ref "D5") (pin "2") (pinfunction "2_2") (pintype "passive"))
    )
    (net (code "44") (name "Net-(D4-Pad6)") (class "Default")
      (node (ref "D4") (pin "6") (pinfunction "6_6") (pintype "passive"))
      (node (ref "D5") (pin "1") (pinfunction "1_1") (pintype "passive"))
    )
    (net (code "45") (name "Net-(D6-Pad1)") (class "Default")
      (node (ref "D6") (pin "1") (pinfunction "1_1") (pintype "passive"))
      (node (ref "D7") (pin "6") (pinfunction "6_6") (pintype "passive"))
    )
    (net (code "46") (name "Net-(D6-Pad2)") (class "Default")
      (node (ref "D6") (pin "2") (pinfunction "2_2") (pintype "passive"))
      (node (ref "D7") (pin "5") (pinfunction "5_5") (pintype "passive"))
    )
    (net (code "47") (name "Net-(D6-Pad3)") (class "Default")
      (node (ref "D6") (pin "3") (pinfunction "3_3") (pintype "passive"))
      (node (ref "D7") (pin "4") (pinfunction "4_4") (pintype "passive"))
    )
    (net (code "48") (name "Net-(Q1-GATE)") (class "Default")
      (node (ref "Q1") (pin "1") (pinfunction "GATE_1") (pintype "passive"))
      (node (ref "R19") (pin "2") (pinfunction "2_2") (pintype "passive"))
      (node (ref "R6") (pin "2") (pinfunction "2_2") (pintype "passive"))
    )
    (net (code "49") (name "Net-(Q2-DRAIN)") (class "Default")
      (node (ref "Q2") (pin "3") (pinfunction "DRAIN_3") (pintype "passive"))
      (node (ref "R3") (pin "1") (pinfunction "1_1") (pintype "passive"))
      (node (ref "S1") (pin "2") (pinfunction "2_2") (pintype "passive"))
    )
    (net (code "50") (name "Net-(Q2-GATE)") (class "Default")
      (node (ref "Q2") (pin "1") (pinfunction "GATE_1") (pintype "passive"))
      (node (ref "R15") (pin "2") (pinfunction "2_2") (pintype "passive"))
      (node (ref "R5") (pin "2") (pinfunction "2_2") (pintype "passive"))
    )
    (net (code "51") (name "Net-(Q3-GATE)") (class "Default")
      (node (ref "Q3") (pin "1") (pinfunction "GATE_1") (pintype "passive"))
      (node (ref "R13") (pin "2") (pinfunction "2_2") (pintype "passive"))
      (node (ref "R20") (pin "2") (pinfunction "2_2") (pintype "passive"))
    )
    (net (code "52") (name "Net-(Q4-GATE)") (class "Default")
      (node (ref "Q4") (pin "1") (pinfunction "GATE_1") (pintype "passive"))
      (node (ref "R14") (pin "2") (pinfunction "2_2") (pintype "passive"))
      (node (ref "R21") (pin "2") (pinfunction "2_2") (pintype "passive"))
    )
    (net (code "53") (name "Net-(U4-SW)") (class "Default")
      (node (ref "L1") (pin "2") (pinfunction "2_2") (pintype "passive"))
      (node (ref "U4") (pin "4") (pinfunction "SW_4") (pintype "passive"))
    )
    (net (code "54") (name "VPIEZO") (class "Default")
      (node (ref "C5") (pin "2") (pinfunction "2_2") (pintype "passive"))
      (node (ref "D5") (pin "4") (pinfunction "4_4") (pintype "passive"))
      (node (ref "D5") (pin "5") (pinfunction "5_5") (pintype "passive"))
      (node (ref "D5") (pin "6") (pinfunction "6_6") (pintype "passive"))
      (node (ref "D6") (pin "4") (pinfunction "4_4") (pintype "passive"))
      (node (ref "D6") (pin "5") (pinfunction "5_5") (pintype "passive"))
      (node (ref "D6") (pin "6") (pinfunction "6_6") (pintype "passive"))
      (node (ref "R3") (pin "2") (pinfunction "2_2") (pintype "passive"))
      (node (ref "R9") (pin "2") (pinfunction "2_2") (pintype "passive"))
      (node (ref "S1") (pin "1") (pinfunction "1_1") (pintype "passive"))
      (node (ref "TP5") (pin "1") (pinfunction "TP_1") (pintype "passive"))
      (node (ref "U4") (pin "5") (pinfunction "OUT_5") (pintype "passive"))
    )
    (net (code "55") (name "unconnected-(J1-KEY-Pad7)") (class "Default")
      (node (ref "J1") (pin "7") (pinfunction "KEY_7") (pintype "passive"))
    )
    (net (code "56") (name "unconnected-(J1-NC{slash}TDI-Pad8)") (class "Default")
      (node (ref "J1") (pin "8") (pinfunction "NC/TDI_8") (pintype "bidirectional"))
    )
    (net (code "57") (name "unconnected-(J1-SWO{slash}TDO-Pad6)") (class "Default")
      (node (ref "J1") (pin "6") (pinfunction "SWO/TDO_6") (pintype "bidirectional"))
    )
    (net (code "58") (name "unconnected-(J2-Green_Anode-Pad11)") (class "Default")
      (node (ref "J2") (pin "11") (pinfunction "Green_Anode_11") (pintype "passive"))
    )
    (net (code "59") (name "unconnected-(J2-Green_Cathode-Pad12)") (class "Default")
      (node (ref "J2") (pin "12") (pinfunction "Green_Cathode_12") (pintype "passive"))
    )
    (net (code "60") (name "unconnected-(J2-Yellow_Anode-Pad9)") (class "Default")
      (node (ref "J2") (pin "9") (pinfunction "Yellow_Anode_9") (pintype "passive"))
    )
    (net (code "61") (name "unconnected-(J2-Yellow_Cathode-Pad10)") (class "Default")
      (node (ref "J2") (pin "10") (pinfunction "Yellow_Cathode_10") (pintype "passive"))
    )
    (net (code "62") (name "unconnected-(OLED1-D2-Pad15)") (class "Default")
      (node (ref "OLED1") (pin "15") (pinfunction "D2_15") (pintype "passive"))
    )
    (net (code "63") (name "unconnected-(OLED1-IREF-Pad21)") (class "Default")
      (node (ref "OLED1") (pin "21") (pinfunction "IREF_21") (pintype "passive"))
    )
    (net (code "64") (name "unconnected-(OLED1-NC-Pad4)") (class "Default")
      (node (ref "OLED1") (pin "4") (pinfunction "NC_4") (pintype "passive"))
    )
    (net (code "65") (name "unconnected-(OLED1-VCC-Pad23)") (class "Default")
      (node (ref "OLED1") (pin "23") (pinfunction "VCC_23") (pintype "passive"))
    )
    (net (code "66") (name "unconnected-(OLED1-VCOMH-Pad22)") (class "Default")
      (node (ref "OLED1") (pin "22") (pinfunction "VCOMH_22") (pintype "passive"))
    )
    (net (code "67") (name "unconnected-(U1A-PA2-Pad12)") (class "Default")
      (node (ref "U1") (pin "12") (pinfunction "PA2_12") (pintype "bidirectional"))
    )
    (net (code "68") (name "unconnected-(U1A-PA8-Pad29)") (class "Default")
      (node (ref "U1") (pin "29") (pinfunction "PA8_29") (pintype "bidirectional"))
    )
    (net (code "69") (name "unconnected-(U1A-PA11-Pad32)") (class "Default")
      (node (ref "U1") (pin "32") (pinfunction "PA11_32") (pintype "bidirectional"))
    )
    (net (code "70") (name "unconnected-(U1A-PA12-Pad33)") (class "Default")
      (node (ref "U1") (pin "33") (pinfunction "PA12_33") (pintype "bidirectional"))
    )
    (net (code "71") (name "unconnected-(U1A-PA15-Pad38)") (class "Default")
      (node (ref "U1") (pin "38") (pinfunction "PA15_38") (pintype "bidirectional"))
    )
    (net (code "72") (name "unconnected-(U1A-PB1-Pad19)") (class "Default")
      (node (ref "U1") (pin "19") (pinfunction "PB1_19") (pintype "bidirectional"))
    )
    (net (code "73") (name "unconnected-(U1A-PB2-Pad20)") (class "Default")
      (node (ref "U1") (pin "20") (pinfunction "PB2_20") (pintype "bidirectional"))
    )
    (net (code "74") (name "unconnected-(U1A-PB3-Pad39)") (class "Default")
      (node (ref "U1") (pin "39") (pinfunction "PB3_39") (pintype "bidirectional"))
    )
    (net (code "75") (name "unconnected-(U1A-PB6-Pad42)") (class "Default")
      (node (ref "U1") (pin "42") (pinfunction "PB6_42") (pintype "bidirectional"))
    )
    (net (code "76") (name "unconnected-(U1A-PB7-Pad43)") (class "Default")
      (node (ref "U1") (pin "43") (pinfunction "PB7_43") (pintype "bidirectional"))
    )
    (net (code "77") (name "unconnected-(U1A-PB8-Pad45)") (class "Default")
      (node (ref "U1") (pin "45") (pinfunction "PB8_45") (pintype "bidirectional"))
    )
    (net (code "78") (name "unconnected-(U1A-PB9-Pad46)") (class "Default")
      (node (ref "U1") (pin "46") (pinfunction "PB9_46") (pintype "bidirectional"))
    )
    (net (code "79") (name "unconnected-(U1A-PB10-Pad21)") (class "Default")
      (node (ref "U1") (pin "21") (pinfunction "PB10_21") (pintype "bidirectional"))
    )
    (net (code "80") (name "unconnected-(U1A-PB11-Pad22)") (class "Default")
      (node (ref "U1") (pin "22") (pinfunction "PB11_22") (pintype "bidirectional"))
    )
    (net (code "81") (name "unconnected-(U1A-PB12-Pad25)") (class "Default")
      (node (ref "U1") (pin "25") (pinfunction "PB12_25") (pintype "bidirectional"))
    )
    (net (code "82") (name "unconnected-(U1A-PB13-Pad26)") (class "Default")
      (node (ref "U1") (pin "26") (pinfunction "PB13_26") (pintype "bidirectional"))
    )
    (net (code "83") (name "unconnected-(U1A-PB14-Pad27)") (class "Default")
      (node (ref "U1") (pin "27") (pinfunction "PB14_27") (pintype "bidirectional"))
    )
    (net (code "84") (name "unconnected-(U1A-PB15-Pad28)") (class "Default")
      (node (ref "U1") (pin "28") (pinfunction "PB15_28") (pintype "bidirectional"))
    )
    (net (code "85") (name "unconnected-(U1A-PC13-Pad2)") (class "Default")
      (node (ref "U1") (pin "2") (pinfunction "PC13_2") (pintype "bidirectional"))
    )
    (net (code "86") (name "unconnected-(U1A-PC14-OSC32_IN(PC14)-Pad3)") (class "Default")
      (node (ref "U1") (pin "3") (pinfunction "PC14-OSC32_IN(PC14)_3") (pintype "bidirectional"))
    )
    (net (code "87") (name "unconnected-(U1A-PC15-OSC32_OUT(PC15)-Pad4)") (class "Default")
      (node (ref "U1") (pin "4") (pinfunction "PC15-OSC32_OUT(PC15)_4") (pintype "bidirectional"))
    )
    (net (code "88") (name "unconnected-(U1A-PF6-Pad35)") (class "Default")
      (node (ref "U1") (pin "35") (pinfunction "PF6_35") (pintype "bidirectional"))
    )
    (net (code "89") (name "unconnected-(U1A-PF7-Pad36)") (class "Default")
      (node (ref "U1") (pin "36") (pinfunction "PF7_36") (pintype "bidirectional"))
    )
  )
)
